# noWOL.net
KiCad netlist of a schematic drawn in EAGLE
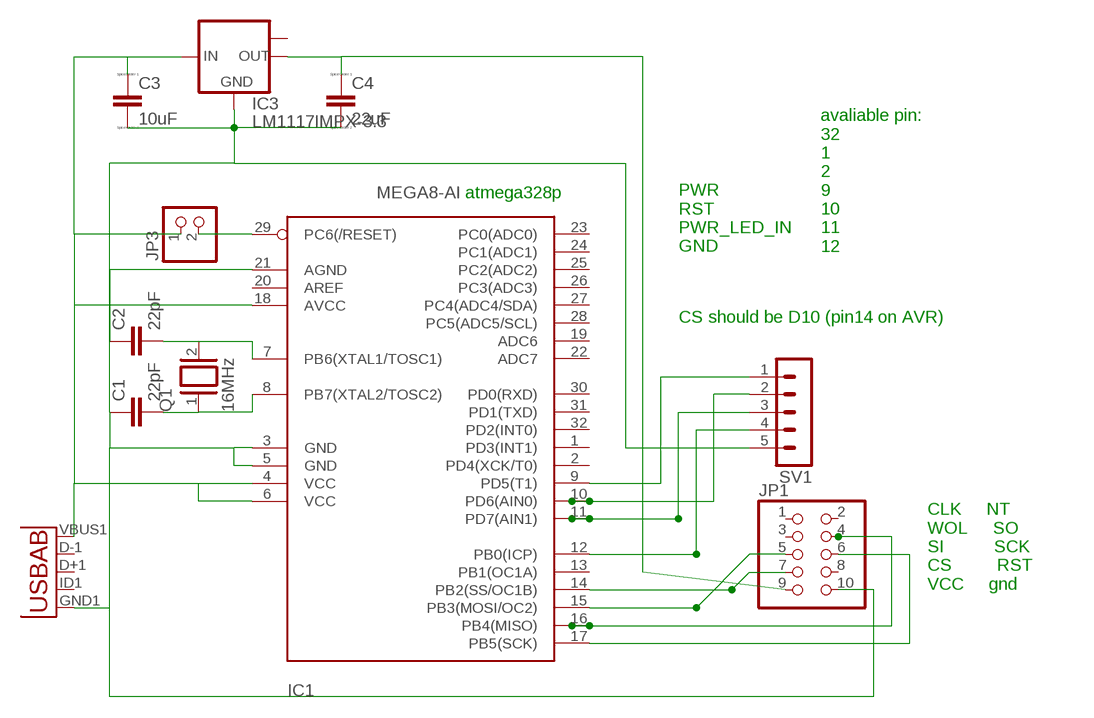
[diagram p0: schematic, sheet 1]

(export (version "E")
  (design (tool "Eeschema 10.0.6"))
  (components
    (comp (ref "C1")
      (value "22pF")
      (footprint "eagle-import:C0603")
      (libsource (lib "eagle-import") (part "C-EUC0603"))
    )
    (comp (ref "C2")
      (value "22pF")
      (footprint "eagle-import:C0603")
      (libsource (lib "eagle-import") (part "C-EUC0603"))
    )
    (comp (ref "C3")
      (value "10uF")
      (footprint "eagle-import:C0603")
      (libsource (lib "eagle-import") (part "CC0603"))
    )
    (comp (ref "C4")
      (value "22uF")
      (footprint "eagle-import:C0603")
      (libsource (lib "eagle-import") (part "CC0603"))
    )
    (comp (ref "IC1")
      (value "MEGA8-AI")
      (footprint "eagle-import:TQFP32-08")
      (libsource (lib "eagle-import") (part "MEGA8-AI"))
    )
    (comp (ref "IC3")
      (value "LM1117IMPX-3.3")
      (footprint "eagle-import:SOT223")
      (libsource (lib "eagle-import") (part "LM1117IMPX-3.3"))
    )
    (comp (ref "JP1")
      (value "PINHD-2X5")
      (footprint "eagle-import:2X05")
      (libsource (lib "eagle-import") (part "PINHD-2X5"))
    )
    (comp (ref "JP3")
      (value "PINHD-1X2")
      (footprint "eagle-import:1X02")
      (libsource (lib "eagle-import") (part "PINHD-1X2"))
    )
    (comp (ref "Q1")
      (value "16MHz")
      (footprint "eagle-import:QS")
      (libsource (lib "eagle-import") (part "XTAL/S"))
    )
    (comp (ref "SV1")
      (value "MA05-1")
      (footprint "eagle-import:MA05-1")
      (libsource (lib "eagle-import") (part "MA05-1"))
    )
    (comp (ref "U1")
      (value "USB\"\"")
      (footprint "eagle-import:USB-MICRO-SMD")
      (libsource (lib "eagle-import") (part "USB{dblquote}{dblquote}"))
    )
  )
  (nets
    (net (code "1") (name "Net-(IC1-AGND)") (class "Default")
      (node (ref "C1") (pin "1") (pinfunction "1_1") (pintype "passive"))
      (node (ref "C2") (pin "1") (pinfunction "1_1") (pintype "passive"))
      (node (ref "C3") (pin "2") (pinfunction "2_2") (pintype "passive"))
      (node (ref "C4") (pin "2") (pinfunction "2_2") (pintype "passive"))
      (node (ref "IC1") (pin "21") (pinfunction "AGND_21") (pintype "bidirectional"))
      (node (ref "IC1") (pin "3") (pinfunction "GND_3") (pintype "bidirectional"))
      (node (ref "IC1") (pin "5") (pinfunction "GND_5") (pintype "bidirectional"))
      (node (ref "IC3") (pin "1") (pinfunction "GND_1") (pintype "input"))
      (node (ref "JP1") (pin "10") (pinfunction "10_10") (pintype "passive"))
      (node (ref "SV1") (pin "5") (pinfunction "5_5") (pintype "passive"))
      (node (ref "U1") (pin "GND1") (pinfunction "GND_GND1") (pintype "bidirectional"))
    )
    (net (code "2") (name "Net-(IC1-AVCC)") (class "Default")
      (node (ref "C3") (pin "1") (pinfunction "1_1") (pintype "passive"))
      (node (ref "IC1") (pin "18") (pinfunction "AVCC_18") (pintype "bidirectional"))
      (node (ref "IC1") (pin "4") (pinfunction "VCC_4") (pintype "bidirectional"))
      (node (ref "IC1") (pin "6") (pinfunction "VCC_6") (pintype "bidirectional"))
      (node (ref "IC3") (pin "3") (pinfunction "IN_3") (pintype "input"))
      (node (ref "JP3") (pin "1") (pinfunction "1_1") (pintype "passive"))
      (node (ref "U1") (pin "VBUS1") (pinfunction "VBUS_VBUS1") (pintype "bidirectional"))
    )
    (net (code "3") (name "Net-(IC1-PB0(ICP))") (class "Default")
      (node (ref "IC1") (pin "12") (pinfunction "PB0(ICP)_12") (pintype "bidirectional"))
      (node (ref "SV1") (pin "4") (pinfunction "4_4") (pintype "passive"))
    )
    (net (code "4") (name "Net-(IC1-PB2(SS{slash}OC1B))") (class "Default")
      (node (ref "IC1") (pin "14") (pinfunction "PB2(SS/OC1B)_14") (pintype "bidirectional"))
      (node (ref "JP1") (pin "7") (pinfunction "7_7") (pintype "passive"))
    )
    (net (code "5") (name "Net-(IC1-PB3(MOSI{slash}OC2))") (class "Default")
      (node (ref "IC1") (pin "15") (pinfunction "PB3(MOSI/OC2)_15") (pintype "bidirectional"))
      (node (ref "JP1") (pin "5") (pinfunction "5_5") (pintype "passive"))
    )
    (net (code "6") (name "Net-(IC1-PB4(MISO))") (class "Default")
      (node (ref "IC1") (pin "16") (pinfunction "PB4(MISO)_16") (pintype "bidirectional"))
      (node (ref "JP1") (pin "4") (pinfunction "4_4") (pintype "passive"))
    )
    (net (code "7") (name "Net-(IC1-PB5(SCK))") (class "Default")
      (node (ref "IC1") (pin "17") (pinfunction "PB5(SCK)_17") (pintype "bidirectional"))
      (node (ref "JP1") (pin "6") (pinfunction "6_6") (pintype "passive"))
    )
    (net (code "8") (name "Net-(IC1-PB6(XTAL1{slash}TOSC1))") (class "Default")
      (node (ref "C2") (pin "2") (pinfunction "2_2") (pintype "passive"))
      (node (ref "IC1") (pin "7") (pinfunction "PB6(XTAL1/TOSC1)_7") (pintype "bidirectional"))
      (node (ref "Q1") (pin "2") (pinfunction "2_2") (pintype "passive"))
    )
    (net (code "9") (name "Net-(IC1-PB7(XTAL2{slash}TOSC2))") (class "Default")
      (node (ref "C1") (pin "2") (pinfunction "2_2") (pintype "passive"))
      (node (ref "IC1") (pin "8") (pinfunction "PB7(XTAL2/TOSC2)_8") (pintype "bidirectional"))
      (node (ref "Q1") (pin "1") (pinfunction "1_1") (pintype "passive"))
    )
    (net (code "10") (name "Net-(IC1-PC6({slash}RESET))") (class "Default")
      (node (ref "IC1") (pin "29") (pinfunction "PC6(/RESET)_29") (pintype "bidirectional"))
      (node (ref "JP3") (pin "2") (pinfunction "2_2") (pintype "passive"))
    )
    (net (code "11") (name "Net-(IC1-PD5(T1))") (class "Default")
      (node (ref "IC1") (pin "9") (pinfunction "PD5(T1)_9") (pintype "bidirectional"))
      (node (ref "SV1") (pin "1") (pinfunction "1_1") (pintype "passive"))
    )
    (net (code "12") (name "Net-(IC1-PD6(AIN0))") (class "Default")
      (node (ref "IC1") (pin "10") (pinfunction "PD6(AIN0)_10") (pintype "bidirectional"))
      (node (ref "SV1") (pin "2") (pinfunction "2_2") (pintype "passive"))
    )
    (net (code "13") (name "Net-(IC1-PD7(AIN1))") (class "Default")
      (node (ref "IC1") (pin "11") (pinfunction "PD7(AIN1)_11") (pintype "bidirectional"))
      (node (ref "SV1") (pin "3") (pinfunction "3_3") (pintype "passive"))
    )
    (net (code "14") (name "Net-(IC3-OUT)") (class "Default")
      (node (ref "C4") (pin "1") (pinfunction "1_1") (pintype "passive"))
      (node (ref "IC3") (pin "2") (pinfunction "OUT_2") (pintype "passive"))
      (node (ref "JP1") (pin "9") (pinfunction "9_9") (pintype "passive"))
    )
    (net (code "15") (name "unconnected-(IC1-ADC6-Pad19)") (class "Default")
      (node (ref "IC1") (pin "19") (pinfunction "ADC6_19") (pintype "bidirectional"))
    )
    (net (code "16") (name "unconnected-(IC1-ADC7-Pad22)") (class "Default")
      (node (ref "IC1") (pin "22") (pinfunction "ADC7_22") (pintype "bidirectional"))
    )
    (net (code "17") (name "unconnected-(IC1-AREF-Pad20)") (class "Default")
      (node (ref "IC1") (pin "20") (pinfunction "AREF_20") (pintype "bidirectional"))
    )
    (net (code "18") (name "unconnected-(IC1-PB1(OC1A)-Pad13)") (class "Default")
      (node (ref "IC1") (pin "13") (pinfunction "PB1(OC1A)_13") (pintype "bidirectional"))
    )
    (net (code "19") (name "unconnected-(IC1-PC0(ADC0)-Pad23)") (class "Default")
      (node (ref "IC1") (pin "23") (pinfunction "PC0(ADC0)_23") (pintype "bidirectional"))
    )
    (net (code "20") (name "unconnected-(IC1-PC1(ADC1)-Pad24)") (class "Default")
      (node (ref "IC1") (pin "24") (pinfunction "PC1(ADC1)_24") (pintype "bidirectional"))
    )
    (net (code "21") (name "unconnected-(IC1-PC2(ADC2)-Pad25)") (class "Default")
      (node (ref "IC1") (pin "25") (pinfunction "PC2(ADC2)_25") (pintype "bidirectional"))
    )
    (net (code "22") (name "unconnected-(IC1-PC3(ADC3)-Pad26)") (class "Default")
      (node (ref "IC1") (pin "26") (pinfunction "PC3(ADC3)_26") (pintype "bidirectional"))
    )
    (net (code "23") (name "unconnected-(IC1-PC4(ADC4{slash}SDA)-Pad27)") (class "Default")
      (node (ref "IC1") (pin "27") (pinfunction "PC4(ADC4/SDA)_27") (pintype "bidirectional"))
    )
    (net (code "24") (name "unconnected-(IC1-PC5(ADC5{slash}SCL)-Pad28)") (class "Default")
      (node (ref "IC1") (pin "28") (pinfunction "PC5(ADC5/SCL)_28") (pintype "bidirectional"))
    )
    (net (code "25") (name "unconnected-(IC1-PD0(RXD)-Pad30)") (class "Default")
      (node (ref "IC1") (pin "30") (pinfunction "PD0(RXD)_30") (pintype "bidirectional"))
    )
    (net (code "26") (name "unconnected-(IC1-PD1(TXD)-Pad31)") (class "Default")
      (node (ref "IC1") (pin "31") (pinfunction "PD1(TXD)_31") (pintype "bidirectional"))
    )
    (net (code "27") (name "unconnected-(IC1-PD2(INT0)-Pad32)") (class "Default")
      (node (ref "IC1") (pin "32") (pinfunction "PD2(INT0)_32") (pintype "bidirectional"))
    )
    (net (code "28") (name "unconnected-(IC1-PD3(INT1)-Pad1)") (class "Default")
      (node (ref "IC1") (pin "1") (pinfunction "PD3(INT1)_1") (pintype "bidirectional"))
    )
    (net (code "29") (name "unconnected-(IC1-PD4(XCK{slash}T0)-Pad2)") (class "Default")
      (node (ref "IC1") (pin "2") (pinfunction "PD4(XCK/T0)_2") (pintype "bidirectional"))
    )
    (net (code "30") (name "unconnected-(IC3-OUT1-PadTAB)") (class "Default")
      (node (ref "IC3") (pin "TAB") (pinfunction "OUT1_TAB") (pintype "passive"))
    )
    (net (code "31") (name "unconnected-(JP1-Pad1)") (class "Default")
      (node (ref "JP1") (pin "1") (pinfunction "1_1") (pintype "passive"))
    )
    (net (code "32") (name "unconnected-(JP1-Pad2)") (class "Default")
      (node (ref "JP1") (pin "2") (pinfunction "2_2") (pintype "passive"))
    )
    (net (code "33") (name "unconnected-(JP1-Pad3)") (class "Default")
      (node (ref "JP1") (pin "3") (pinfunction "3_3") (pintype "passive"))
    )
    (net (code "34") (name "unconnected-(JP1-Pad8)") (class "Default")
      (node (ref "JP1") (pin "8") (pinfunction "8_8") (pintype "passive"))
    )
    (net (code "35") (name "unconnected-(U1-D+-PadD+1)") (class "Default")
      (node (ref "U1") (pin "D+1") (pinfunction "D+_D+1") (pintype "bidirectional"))
    )
    (net (code "36") (name "unconnected-(U1-D--PadD-1)") (class "Default")
      (node (ref "U1") (pin "D-1") (pinfunction "D-_D-1") (pintype "bidirectional"))
    )
    (net (code "37") (name "unconnected-(U1-USBID-PadID1)") (class "Default")
      (node (ref "U1") (pin "ID1") (pinfunction "USBID_ID1") (pintype "bidirectional"))
    )
  )
)
